# untitled.net
KiCad netlist of a schematic drawn in EAGLE
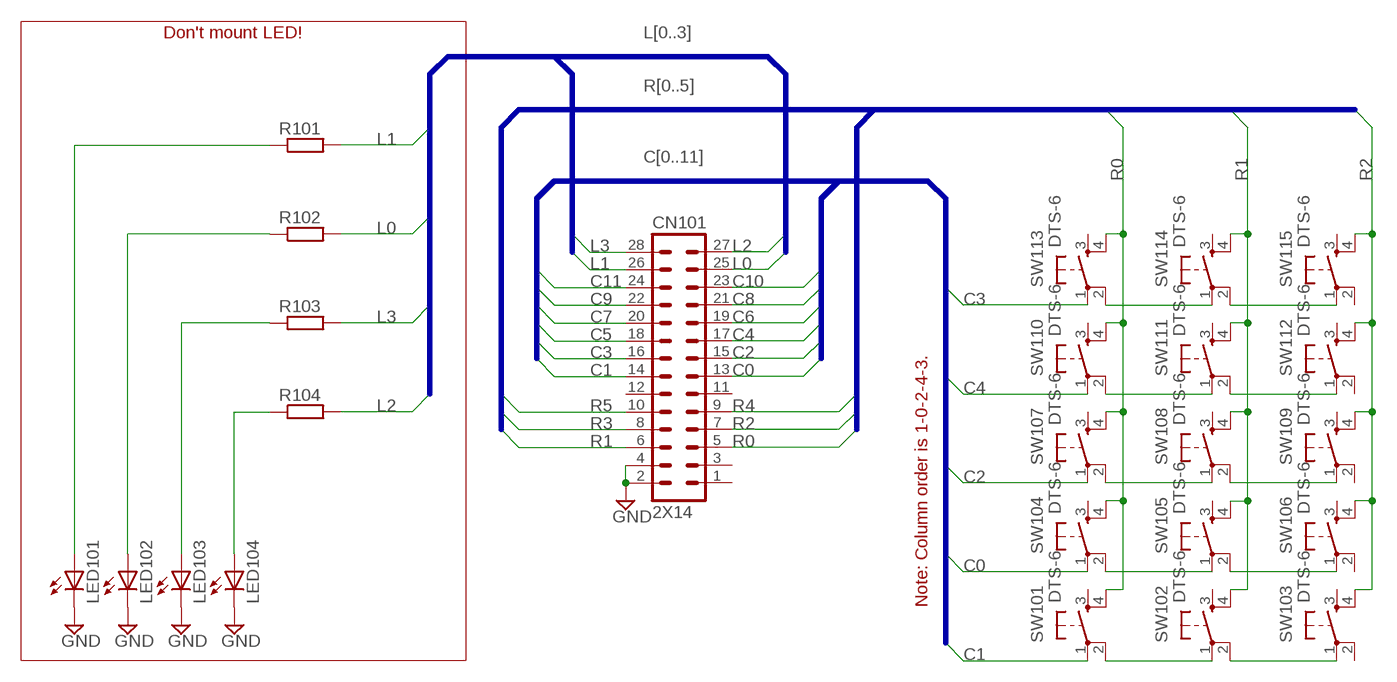
[diagram p0: schematic, sheet 1]

(export (version "E")
  (design (tool "Eeschema 10.0.6"))
  (components
    (comp (ref "CN101")
      (value "2X14")
      (footprint "eagle-import:2MM_14X2")
      (libsource (lib "eagle-import") (part "2X14"))
    )
    (comp (ref "LED101")
      (value "LEDP-LCC-2-BACK")
      (footprint "eagle-import:P-LCC-2-TOPLED-RG")
      (libsource (lib "eagle-import") (part "LEDP-LCC-2-BACK"))
    )
    (comp (ref "LED102")
      (value "LEDP-LCC-2-BACK")
      (footprint "eagle-import:P-LCC-2-TOPLED-RG")
      (libsource (lib "eagle-import") (part "LEDP-LCC-2-BACK"))
    )
    (comp (ref "LED103")
      (value "LEDP-LCC-2-BACK")
      (footprint "eagle-import:P-LCC-2-TOPLED-RG")
      (libsource (lib "eagle-import") (part "LEDP-LCC-2-BACK"))
    )
    (comp (ref "LED104")
      (value "LEDP-LCC-2-BACK")
      (footprint "eagle-import:P-LCC-2-TOPLED-RG")
      (libsource (lib "eagle-import") (part "LEDP-LCC-2-BACK"))
    )
    (comp (ref "R101")
      (value "R-EU_R0402-SS")
      (footprint "eagle-import:R0402-SS")
      (libsource (lib "eagle-import") (part "R-EU_R0402-SS"))
    )
    (comp (ref "R102")
      (value "R-EU_R0402-SS")
      (footprint "eagle-import:R0402-SS")
      (libsource (lib "eagle-import") (part "R-EU_R0402-SS"))
    )
    (comp (ref "R103")
      (value "R-EU_R0402-SS")
      (footprint "eagle-import:R0402-SS")
      (libsource (lib "eagle-import") (part "R-EU_R0402-SS"))
    )
    (comp (ref "R104")
      (value "R-EU_R0402-SS")
      (footprint "eagle-import:R0402-SS")
      (libsource (lib "eagle-import") (part "R-EU_R0402-SS"))
    )
    (comp (ref "SW101")
      (value "DTS-6")
      (footprint "eagle-import:DTS-6")
      (libsource (lib "eagle-import") (part "DTS-6"))
    )
    (comp (ref "SW102")
      (value "DTS-6")
      (footprint "eagle-import:DTS-6")
      (libsource (lib "eagle-import") (part "DTS-6"))
    )
    (comp (ref "SW103")
      (value "DTS-6")
      (footprint "eagle-import:DTS-6")
      (libsource (lib "eagle-import") (part "DTS-6"))
    )
    (comp (ref "SW104")
      (value "DTS-6")
      (footprint "eagle-import:DTS-6")
      (libsource (lib "eagle-import") (part "DTS-6"))
    )
    (comp (ref "SW105")
      (value "DTS-6")
      (footprint "eagle-import:DTS-6")
      (libsource (lib "eagle-import") (part "DTS-6"))
    )
    (comp (ref "SW106")
      (value "DTS-6")
      (footprint "eagle-import:DTS-6")
      (libsource (lib "eagle-import") (part "DTS-6"))
    )
    (comp (ref "SW107")
      (value "DTS-6")
      (footprint "eagle-import:DTS-6")
      (libsource (lib "eagle-import") (part "DTS-6"))
    )
    (comp (ref "SW108")
      (value "DTS-6")
      (footprint "eagle-import:DTS-6")
      (libsource (lib "eagle-import") (part "DTS-6"))
    )
    (comp (ref "SW109")
      (value "DTS-6")
      (footprint "eagle-import:DTS-6")
      (libsource (lib "eagle-import") (part "DTS-6"))
    )
    (comp (ref "SW110")
      (value "DTS-6")
      (footprint "eagle-import:DTS-6")
      (libsource (lib "eagle-import") (part "DTS-6"))
    )
    (comp (ref "SW111")
      (value "DTS-6")
      (footprint "eagle-import:DTS-6")
      (libsource (lib "eagle-import") (part "DTS-6"))
    )
    (comp (ref "SW112")
      (value "DTS-6")
      (footprint "eagle-import:DTS-6")
      (libsource (lib "eagle-import") (part "DTS-6"))
    )
    (comp (ref "SW113")
      (value "DTS-6")
      (footprint "eagle-import:DTS-6")
      (libsource (lib "eagle-import") (part "DTS-6"))
    )
    (comp (ref "SW114")
      (value "DTS-6")
      (footprint "eagle-import:DTS-6")
      (libsource (lib "eagle-import") (part "DTS-6"))
    )
    (comp (ref "SW115")
      (value "DTS-6")
      (footprint "eagle-import:DTS-6")
      (libsource (lib "eagle-import") (part "DTS-6"))
    )
  )
  (nets
    (net (code "1") (name "/C0") (class "Default")
      (node (ref "CN101") (pin "13") (pinfunction "13_13") (pintype "passive"))
      (node (ref "SW104") (pin "1") (pinfunction "1_1") (pintype "passive"))
    )
    (net (code "2") (name "/C1") (class "Default")
      (node (ref "CN101") (pin "14") (pinfunction "14_14") (pintype "passive"))
      (node (ref "SW101") (pin "1") (pinfunction "1_1") (pintype "passive"))
    )
    (net (code "3") (name "/C2") (class "Default")
      (node (ref "CN101") (pin "15") (pinfunction "15_15") (pintype "passive"))
      (node (ref "SW107") (pin "1") (pinfunction "1_1") (pintype "passive"))
    )
    (net (code "4") (name "/C3") (class "Default")
      (node (ref "CN101") (pin "16") (pinfunction "16_16") (pintype "passive"))
      (node (ref "SW113") (pin "1") (pinfunction "1_1") (pintype "passive"))
    )
    (net (code "5") (name "/C4") (class "Default")
      (node (ref "CN101") (pin "17") (pinfunction "17_17") (pintype "passive"))
      (node (ref "SW110") (pin "1") (pinfunction "1_1") (pintype "passive"))
    )
    (net (code "6") (name "/C5") (class "Default")
      (node (ref "CN101") (pin "18") (pinfunction "18_18") (pintype "passive"))
    )
    (net (code "7") (name "/C6") (class "Default")
      (node (ref "CN101") (pin "19") (pinfunction "19_19") (pintype "passive"))
    )
    (net (code "8") (name "/C7") (class "Default")
      (node (ref "CN101") (pin "20") (pinfunction "20_20") (pintype "passive"))
    )
    (net (code "9") (name "/C8") (class "Default")
      (node (ref "CN101") (pin "21") (pinfunction "21_21") (pintype "passive"))
    )
    (net (code "10") (name "/C9") (class "Default")
      (node (ref "CN101") (pin "22") (pinfunction "22_22") (pintype "passive"))
    )
    (net (code "11") (name "/C10") (class "Default")
      (node (ref "CN101") (pin "23") (pinfunction "23_23") (pintype "passive"))
    )
    (net (code "12") (name "/C11") (class "Default")
      (node (ref "CN101") (pin "24") (pinfunction "24_24") (pintype "passive"))
    )
    (net (code "14") (name "/L0") (class "Default")
      (node (ref "CN101") (pin "25") (pinfunction "25_25") (pintype "passive"))
      (node (ref "R102") (pin "2") (pinfunction "2_2") (pintype "passive"))
    )
    (net (code "15") (name "/L1") (class "Default")
      (node (ref "CN101") (pin "26") (pinfunction "26_26") (pintype "passive"))
      (node (ref "R101") (pin "2") (pinfunction "2_2") (pintype "passive"))
    )
    (net (code "16") (name "/L2") (class "Default")
      (node (ref "CN101") (pin "27") (pinfunction "27_27") (pintype "passive"))
      (node (ref "R104") (pin "2") (pinfunction "2_2") (pintype "passive"))
    )
    (net (code "17") (name "/L3") (class "Default")
      (node (ref "CN101") (pin "28") (pinfunction "28_28") (pintype "passive"))
      (node (ref "R103") (pin "2") (pinfunction "2_2") (pintype "passive"))
    )
    (net (code "19") (name "/R0") (class "Default")
      (node (ref "CN101") (pin "5") (pinfunction "5_5") (pintype "passive"))
      (node (ref "SW101") (pin "4") (pinfunction "4_4") (pintype "passive"))
      (node (ref "SW104") (pin "4") (pinfunction "4_4") (pintype "passive"))
      (node (ref "SW107") (pin "4") (pinfunction "4_4") (pintype "passive"))
      (node (ref "SW110") (pin "4") (pinfunction "4_4") (pintype "passive"))
      (node (ref "SW113") (pin "4") (pinfunction "4_4") (pintype "passive"))
    )
    (net (code "20") (name "/R1") (class "Default")
      (node (ref "CN101") (pin "6") (pinfunction "6_6") (pintype "passive"))
      (node (ref "SW102") (pin "4") (pinfunction "4_4") (pintype "passive"))
      (node (ref "SW105") (pin "4") (pinfunction "4_4") (pintype "passive"))
      (node (ref "SW108") (pin "4") (pinfunction "4_4") (pintype "passive"))
      (node (ref "SW111") (pin "4") (pinfunction "4_4") (pintype "passive"))
      (node (ref "SW114") (pin "4") (pinfunction "4_4") (pintype "passive"))
    )
    (net (code "21") (name "/R2") (class "Default")
      (node (ref "CN101") (pin "7") (pinfunction "7_7") (pintype "passive"))
      (node (ref "SW103") (pin "4") (pinfunction "4_4") (pintype "passive"))
      (node (ref "SW106") (pin "4") (pinfunction "4_4") (pintype "passive"))
      (node (ref "SW109") (pin "4") (pinfunction "4_4") (pintype "passive"))
      (node (ref "SW112") (pin "4") (pinfunction "4_4") (pintype "passive"))
      (node (ref "SW115") (pin "4") (pinfunction "4_4") (pintype "passive"))
    )
    (net (code "22") (name "/R3") (class "Default")
      (node (ref "CN101") (pin "8") (pinfunction "8_8") (pintype "passive"))
    )
    (net (code "23") (name "/R4") (class "Default")
      (node (ref "CN101") (pin "9") (pinfunction "9_9") (pintype "passive"))
    )
    (net (code "24") (name "/R5") (class "Default")
      (node (ref "CN101") (pin "10") (pinfunction "10_10") (pintype "passive"))
    )
    (net (code "26") (name "GND") (class "Default")
      (node (ref "CN101") (pin "2") (pinfunction "2_2") (pintype "passive"))
      (node (ref "CN101") (pin "4") (pinfunction "4_4") (pintype "passive"))
      (node (ref "LED101") (pin "C") (pinfunction "C_C") (pintype "passive"))
      (node (ref "LED102") (pin "C") (pinfunction "C_C") (pintype "passive"))
      (node (ref "LED103") (pin "C") (pinfunction "C_C") (pintype "passive"))
      (node (ref "LED104") (pin "C") (pinfunction "C_C") (pintype "passive"))
    )
    (net (code "27") (name "Net-(LED101-PadA)") (class "Default")
      (node (ref "LED101") (pin "A") (pinfunction "A_A") (pintype "passive"))
      (node (ref "R101") (pin "1") (pinfunction "1_1") (pintype "passive"))
    )
    (net (code "28") (name "Net-(LED102-PadA)") (class "Default")
      (node (ref "LED102") (pin "A") (pinfunction "A_A") (pintype "passive"))
      (node (ref "R102") (pin "1") (pinfunction "1_1") (pintype "passive"))
    )
    (net (code "29") (name "Net-(LED103-PadA)") (class "Default")
      (node (ref "LED103") (pin "A") (pinfunction "A_A") (pintype "passive"))
      (node (ref "R103") (pin "1") (pinfunction "1_1") (pintype "passive"))
    )
    (net (code "30") (name "Net-(LED104-PadA)") (class "Default")
      (node (ref "LED104") (pin "A") (pinfunction "A_A") (pintype "passive"))
      (node (ref "R104") (pin "1") (pinfunction "1_1") (pintype "passive"))
    )
    (net (code "31") (name "Net-(SW101-Pad2)") (class "Default")
      (node (ref "SW101") (pin "2") (pinfunction "2_2") (pintype "passive"))
      (node (ref "SW102") (pin "1") (pinfunction "1_1") (pintype "passive"))
    )
    (net (code "32") (name "Net-(SW102-Pad2)") (class "Default")
      (node (ref "SW102") (pin "2") (pinfunction "2_2") (pintype "passive"))
      (node (ref "SW103") (pin "1") (pinfunction "1_1") (pintype "passive"))
    )
    (net (code "33") (name "Net-(SW104-Pad2)") (class "Default")
      (node (ref "SW104") (pin "2") (pinfunction "2_2") (pintype "passive"))
      (node (ref "SW105") (pin "1") (pinfunction "1_1") (pintype "passive"))
    )
    (net (code "34") (name "Net-(SW105-Pad2)") (class "Default")
      (node (ref "SW105") (pin "2") (pinfunction "2_2") (pintype "passive"))
      (node (ref "SW106") (pin "1") (pinfunction "1_1") (pintype "passive"))
    )
    (net (code "35") (name "Net-(SW107-Pad2)") (class "Default")
      (node (ref "SW107") (pin "2") (pinfunction "2_2") (pintype "passive"))
      (node (ref "SW108") (pin "1") (pinfunction "1_1") (pintype "passive"))
    )
    (net (code "36") (name "Net-(SW108-Pad2)") (class "Default")
      (node (ref "SW108") (pin "2") (pinfunction "2_2") (pintype "passive"))
      (node (ref "SW109") (pin "1") (pinfunction "1_1") (pintype "passive"))
    )
    (net (code "37") (name "Net-(SW110-Pad2)") (class "Default")
      (node (ref "SW110") (pin "2") (pinfunction "2_2") (pintype "passive"))
      (node (ref "SW111") (pin "1") (pinfunction "1_1") (pintype "passive"))
    )
    (net (code "38") (name "Net-(SW111-Pad2)") (class "Default")
      (node (ref "SW111") (pin "2") (pinfunction "2_2") (pintype "passive"))
      (node (ref "SW112") (pin "1") (pinfunction "1_1") (pintype "passive"))
    )
    (net (code "39") (name "Net-(SW113-Pad2)") (class "Default")
      (node (ref "SW113") (pin "2") (pinfunction "2_2") (pintype "passive"))
      (node (ref "SW114") (pin "1") (pinfunction "1_1") (pintype "passive"))
    )
    (net (code "40") (name "Net-(SW114-Pad2)") (class "Default")
      (node (ref "SW114") (pin "2") (pinfunction "2_2") (pintype "passive"))
      (node (ref "SW115") (pin "1") (pinfunction "1_1") (pintype "passive"))
    )
    (net (code "41") (name "unconnected-(CN101-Pad1)") (class "Default")
      (node (ref "CN101") (pin "1") (pinfunction "1_1") (pintype "passive"))
    )
    (net (code "42") (name "unconnected-(CN101-Pad3)") (class "Default")
      (node (ref "CN101") (pin "3") (pinfunction "3_3") (pintype "passive"))
    )
    (net (code "43") (name "unconnected-(CN101-Pad11)") (class "Default")
      (node (ref "CN101") (pin "11") (pinfunction "11_11") (pintype "passive"))
    )
    (net (code "44") (name "unconnected-(CN101-Pad12)") (class "Default")
      (node (ref "CN101") (pin "12") (pinfunction "12_12") (pintype "passive"))
    )
    (net (code "45") (name "unconnected-(SW101-Pad3)") (class "Default")
      (node (ref "SW101") (pin "3") (pinfunction "3_3") (pintype "passive"))
    )
    (net (code "46") (name "unconnected-(SW102-Pad3)") (class "Default")
      (node (ref "SW102") (pin "3") (pinfunction "3_3") (pintype "passive"))
    )
    (net (code "47") (name "unconnected-(SW103-Pad2)") (class "Default")
      (node (ref "SW103") (pin "2") (pinfunction "2_2") (pintype "passive"))
    )
    (net (code "48") (name "unconnected-(SW103-Pad3)") (class "Default")
      (node (ref "SW103") (pin "3") (pinfunction "3_3") (pintype "passive"))
    )
    (net (code "49") (name "unconnected-(SW104-Pad3)") (class "Default")
      (node (ref "SW104") (pin "3") (pinfunction "3_3") (pintype "passive"))
    )
    (net (code "50") (name "unconnected-(SW105-Pad3)") (class "Default")
      (node (ref "SW105") (pin "3") (pinfunction "3_3") (pintype "passive"))
    )
    (net (code "51") (name "unconnected-(SW106-Pad2)") (class "Default")
      (node (ref "SW106") (pin "2") (pinfunction "2_2") (pintype "passive"))
    )
    (net (code "52") (name "unconnected-(SW106-Pad3)") (class "Default")
      (node (ref "SW106") (pin "3") (pinfunction "3_3") (pintype "passive"))
    )
    (net (code "53") (name "unconnected-(SW107-Pad3)") (class "Default")
      (node (ref "SW107") (pin "3") (pinfunction "3_3") (pintype "passive"))
    )
    (net (code "54") (name "unconnected-(SW108-Pad3)") (class "Default")
      (node (ref "SW108") (pin "3") (pinfunction "3_3") (pintype "passive"))
    )
    (net (code "55") (name "unconnected-(SW109-Pad2)") (class "Default")
      (node (ref "SW109") (pin "2") (pinfunction "2_2") (pintype "passive"))
    )
    (net (code "56") (name "unconnected-(SW109-Pad3)") (class "Default")
      (node (ref "SW109") (pin "3") (pinfunction "3_3") (pintype "passive"))
    )
    (net (code "57") (name "unconnected-(SW110-Pad3)") (class "Default")
      (node (ref "SW110") (pin "3") (pinfunction "3_3") (pintype "passive"))
    )
    (net (code "58") (name "unconnected-(SW111-Pad3)") (class "Default")
      (node (ref "SW111") (pin "3") (pinfunction "3_3") (pintype "passive"))
    )
    (net (code "59") (name "unconnected-(SW112-Pad2)") (class "Default")
      (node (ref "SW112") (pin "2") (pinfunction "2_2") (pintype "passive"))
    )
    (net (code "60") (name "unconnected-(SW112-Pad3)") (class "Default")
      (node (ref "SW112") (pin "3") (pinfunction "3_3") (pintype "passive"))
    )
    (net (code "61") (name "unconnected-(SW113-Pad3)") (class "Default")
      (node (ref "SW113") (pin "3") (pinfunction "3_3") (pintype "passive"))
    )
    (net (code "62") (name "unconnected-(SW114-Pad3)") (class "Default")
      (node (ref "SW114") (pin "3") (pinfunction "3_3") (pintype "passive"))
    )
    (net (code "63") (name "unconnected-(SW115-Pad2)") (class "Default")
      (node (ref "SW115") (pin "2") (pinfunction "2_2") (pintype "passive"))
    )
    (net (code "64") (name "unconnected-(SW115-Pad3)") (class "Default")
      (node (ref "SW115") (pin "3") (pinfunction "3_3") (pintype "passive"))
    )
  )
)
